# omnibothub-power-one.net
KiCad netlist of a schematic drawn in Altium Designer
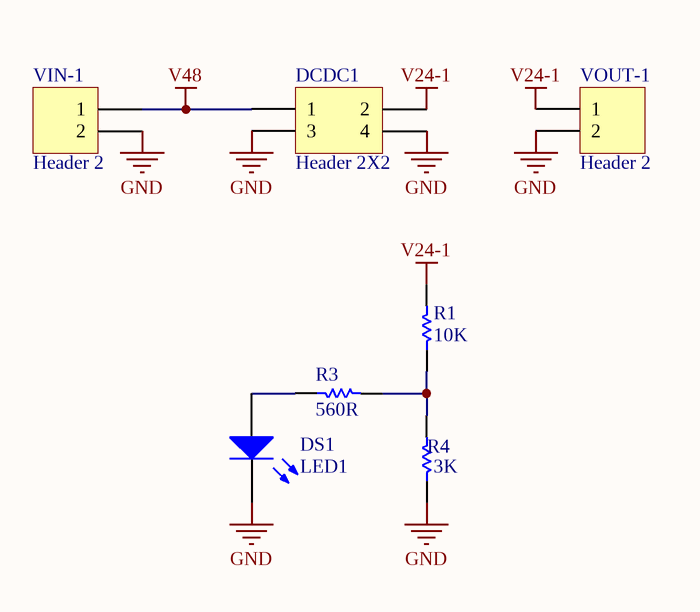
[diagram p0: omnibothub-power-one.SchDoc]

(export (version "E")
  (design (tool "Eeschema 10.0.6"))
  (components
    (comp (ref "DCDC1")
      (value "Header 2X2")
      (footprint "DCDC-1")
      (description "Header, 2-Pin, Dual row")
      (fields (field (name "PUBLISHER") "Altium Limited"))
      (libsource (lib "Miscellaneous Connectors") (part "Header 2X2"))
    )
    (comp (ref "DS1")
      (value "LED1")
      (footprint "SMDLED")
      (description "Typical RED, GREEN, YELLOW, AMBER GaAs LED")
      (fields (field (name "PUBLISHER") "Altium Limited"))
      (libsource (lib "EXPLORER") (part "LED2"))
    )
    (comp (ref "R1")
      (value "10K")
      (footprint "R0805")
      (description "0603")
      (libsource (lib "stm32f429i") (part "Res2"))
    )
    (comp (ref "R3")
      (value "560R")
      (footprint "R0603")
      (description "0603")
      (libsource (lib "stm32f429i") (part "Res2"))
    )
    (comp (ref "R4")
      (value "3K")
      (footprint "R0805")
      (description "0603")
      (libsource (lib "stm32f429i") (part "Res2"))
    )
    (comp (ref "VIN-1")
      (value "Header 2")
      (footprint "AMASS-XT30PW-M")
      (description "Header, 2-Pin")
      (fields (field (name "PUBLISHER") "Altium Limited"))
      (libsource (lib "Miscellaneous Connectors") (part "Header 2"))
    )
    (comp (ref "VOUT-1")
      (value "Header 2")
      (footprint "AMASS-XT30PW-M")
      (description "Header, 2-Pin")
      (fields (field (name "PUBLISHER") "Altium Limited"))
      (libsource (lib "") (part "Header 2_1"))
    )
  )
  (nets
    (net (code "1") (name "GND") (class "Default")
      (node (ref "DCDC1") (pin "3") (pinfunction "3_3") (pintype "passive"))
      (node (ref "DCDC1") (pin "4") (pinfunction "4_4") (pintype "passive"))
      (node (ref "DS1") (pin "2") (pinfunction "K_2") (pintype "passive"))
      (node (ref "R4") (pin "1") (pinfunction "1_1") (pintype "passive"))
      (node (ref "VIN-1") (pin "2") (pinfunction "2_2") (pintype "passive"))
      (node (ref "VOUT-1") (pin "2") (pinfunction "2_2") (pintype "passive"))
    )
    (net (code "2") (name "Net-(DS1-A)") (class "Default")
      (node (ref "DS1") (pin "1") (pinfunction "A_1") (pintype "passive"))
      (node (ref "R3") (pin "1") (pinfunction "1_1") (pintype "passive"))
    )
    (net (code "3") (name "Net-(R1-Pad1)") (class "Default")
      (node (ref "R1") (pin "1") (pinfunction "1_1") (pintype "passive"))
      (node (ref "R3") (pin "2") (pinfunction "2_2") (pintype "passive"))
      (node (ref "R4") (pin "2") (pinfunction "2_2") (pintype "passive"))
    )
    (net (code "4") (name "V24-1") (class "Default")
      (node (ref "DCDC1") (pin "2") (pinfunction "2_2") (pintype "passive"))
      (node (ref "R1") (pin "2") (pinfunction "2_2") (pintype "passive"))
      (node (ref "VOUT-1") (pin "1") (pinfunction "1_1") (pintype "passive"))
    )
    (net (code "5") (name "V48") (class "Default")
      (node (ref "DCDC1") (pin "1") (pinfunction "1_1") (pintype "passive"))
      (node (ref "VIN-1") (pin "1") (pinfunction "1_1") (pintype "passive"))
    )
  )
)
